# CON_DEBUG_10WBOXHDRRAM.net
KiCad netlist of a schematic drawn in Altium Designer
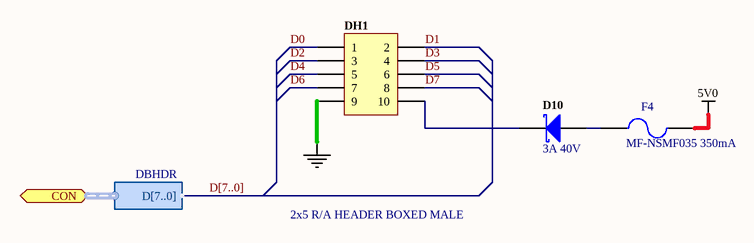
[diagram p0: CON_DEBUG_10WBOXHDRRAM.SchDoc]

(export (version "E")
  (design (tool "Eeschema 10.0.6"))
  (components
    (comp (ref "D10")
      (value "3A 40V")
      (footprint "DIOM5027")
      (description "Schottky Diode, 3A 40V")
      (libsource (lib "altium-import") (part "root_2_DIO-SCHOTTKY-1S_"))
    )
    (comp (ref "DH1")
      (value "2x5 R/A HEADER BOXED MALE")
      (footprint "918510x323")
      (description "Header IDC, 2 x 5 Pin Right-Angle 2.54mm Pitch (Boxed-Male)")
      (libsource (lib "altium-import") (part "root_0_CON-IDC-2x5-M-RA_"))
    )
    (comp (ref "F4")
      (value "MF-NSMF035 350mA")
      (footprint "RESC3216")
      (description "Multifuse, SMD 1206, 350mA")
      (libsource (lib "AltiumDesignLibrary") (part "MULTIFUSE"))
    )
  )
  (nets
    (net (code "3") (name "/D0") (class "Default")
      (node (ref "DH1") (pin "1") (pinfunction "1_1") (pintype "passive"))
    )
    (net (code "4") (name "/D1") (class "Default")
      (node (ref "DH1") (pin "2") (pinfunction "2_2") (pintype "passive"))
    )
    (net (code "5") (name "/D2") (class "Default")
      (node (ref "DH1") (pin "3") (pinfunction "3_3") (pintype "passive"))
    )
    (net (code "6") (name "/D3") (class "Default")
      (node (ref "DH1") (pin "4") (pinfunction "4_4") (pintype "passive"))
    )
    (net (code "7") (name "/D4") (class "Default")
      (node (ref "DH1") (pin "5") (pinfunction "5_5") (pintype "passive"))
    )
    (net (code "8") (name "/D5") (class "Default")
      (node (ref "DH1") (pin "6") (pinfunction "6_6") (pintype "passive"))
    )
    (net (code "9") (name "/D6") (class "Default")
      (node (ref "DH1") (pin "7") (pinfunction "7_7") (pintype "passive"))
    )
    (net (code "10") (name "/D7") (class "Default")
      (node (ref "DH1") (pin "8") (pinfunction "8_8") (pintype "passive"))
    )
    (net (code "12") (name "5V0") (class "Default")
      (node (ref "F4") (pin "2") (pinfunction "2_2") (pintype "passive"))
    )
    (net (code "13") (name "GND") (class "Default")
      (node (ref "DH1") (pin "9") (pinfunction "9_9") (pintype "passive"))
    )
    (net (code "14") (name "Net-(D10-A)") (class "Default")
      (node (ref "D10") (pin "1") (pinfunction "A_1") (pintype "passive"))
      (node (ref "F4") (pin "1") (pinfunction "1_1") (pintype "passive"))
    )
    (net (code "15") (name "Net-(D10-K)") (class "Default")
      (node (ref "D10") (pin "2") (pinfunction "K_2") (pintype "passive"))
      (node (ref "DH1") (pin "10") (pinfunction "10_10") (pintype "passive"))
    )
  )
)
